# logi-edu.net
KiCad netlist of a schematic drawn in Altium Designer
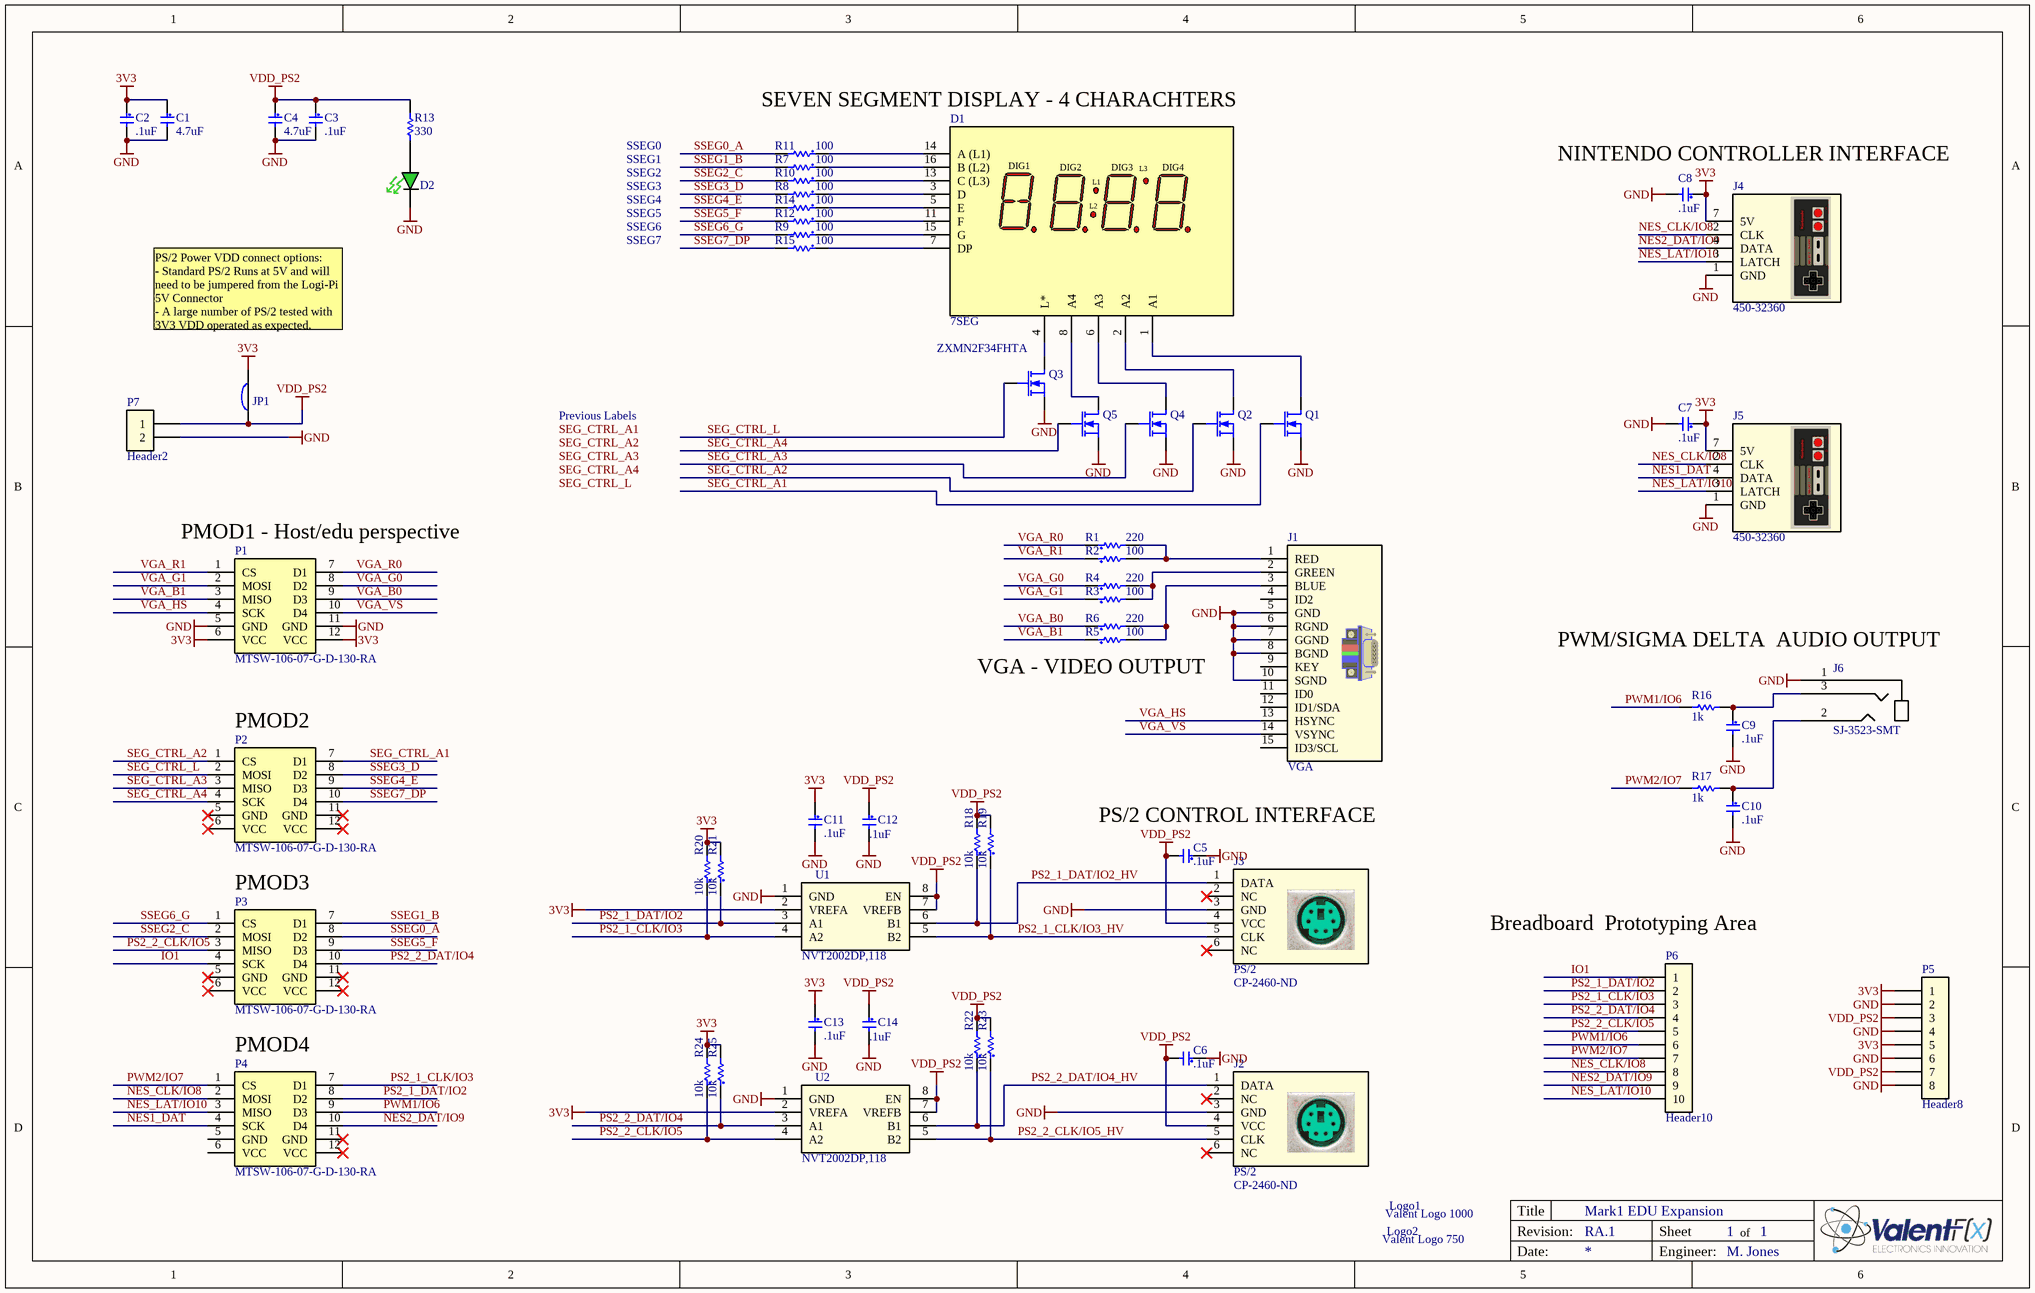
[diagram p0: logi-edu.SchDoc]

(export (version "E")
  (design (tool "Eeschema 10.0.6"))
  (components
    (comp (ref "C1")
      (value "4.7uF")
      (footprint "mRCL:C0603")
      (description "4.7uF 10volts Y5V +80-20% (MLCC) - SMD/SMT 0603")
      (fields
        (field (name "MANUFACTURER") "Murata")
        (field (name "MANUFACTURER PART NUMBER") "GRM188F51A475ZE20D")
      )
      (libsource (lib "mCapacitors") (part "C0603 - GRM188F51A475ZE20D"))
    )
    (comp (ref "C2")
      (value ".1uF")
      (footprint "mRCL:C0603")
      (description "0.1uF 50volts X7R 10% MLCC SMD/SMT 0603")
      (fields
        (field (name "MANUFACTURER") "Murata")
        (field (name "MANUFACTURER PART NUMBER") "GRM188R71H104KA93D")
      )
      (libsource (lib "mCapacitors") (part "C0603 - GRM188R71H104KA93D"))
    )
    (comp (ref "C3")
      (value ".1uF")
      (footprint "mRCL:C0603")
      (description "0.1uF 50volts X7R 10% MLCC SMD/SMT 0603")
      (fields
        (field (name "MANUFACTURER") "Murata")
        (field (name "MANUFACTURER PART NUMBER") "GRM188R71H104KA93D")
      )
      (libsource (lib "mCapacitors") (part "C0603 - GRM188R71H104KA93D"))
    )
    (comp (ref "C4")
      (value "4.7uF")
      (footprint "mRCL:C0603")
      (description "4.7uF 10volts Y5V +80-20% (MLCC) - SMD/SMT 0603")
      (fields
        (field (name "MANUFACTURER") "Murata")
        (field (name "MANUFACTURER PART NUMBER") "GRM188F51A475ZE20D")
      )
      (libsource (lib "mCapacitors") (part "C0603 - GRM188F51A475ZE20D"))
    )
    (comp (ref "C5")
      (value ".1uF")
      (footprint "mRCL:C0603")
      (description "0.1uF 50volts X7R 10% MLCC SMD/SMT 0603")
      (fields
        (field (name "MANUFACTURER") "Murata")
        (field (name "MANUFACTURER PART NUMBER") "GRM188R71H104KA93D")
      )
      (libsource (lib "mCapacitors") (part "C0603 - GRM188R71H104KA93D"))
    )
    (comp (ref "C6")
      (value ".1uF")
      (footprint "mRCL:C0603")
      (description "0.1uF 50volts X7R 10% MLCC SMD/SMT 0603")
      (fields
        (field (name "MANUFACTURER") "Murata")
        (field (name "MANUFACTURER PART NUMBER") "GRM188R71H104KA93D")
      )
      (libsource (lib "mCapacitors") (part "C0603 - GRM188R71H104KA93D"))
    )
    (comp (ref "C7")
      (value ".1uF")
      (footprint "mRCL:C0603")
      (description "0.1uF 50volts X7R 10% MLCC SMD/SMT 0603")
      (fields
        (field (name "MANUFACTURER") "Murata")
        (field (name "MANUFACTURER PART NUMBER") "GRM188R71H104KA93D")
      )
      (libsource (lib "mCapacitors") (part "C0603 - GRM188R71H104KA93D"))
    )
    (comp (ref "C8")
      (value ".1uF")
      (footprint "mRCL:C0603")
      (description "0.1uF 50volts X7R 10% MLCC SMD/SMT 0603")
      (fields
        (field (name "MANUFACTURER") "Murata")
        (field (name "MANUFACTURER PART NUMBER") "GRM188R71H104KA93D")
      )
      (libsource (lib "mCapacitors") (part "C0603 - GRM188R71H104KA93D"))
    )
    (comp (ref "C9")
      (value ".1uF")
      (footprint "mRCL:C0603")
      (description "0.1uF 50volts X7R 10% MLCC SMD/SMT 0603")
      (fields
        (field (name "MANUFACTURER") "Murata")
        (field (name "MANUFACTURER PART NUMBER") "GRM188R71H104KA93D")
      )
      (libsource (lib "mCapacitors") (part "C0603 - GRM188R71H104KA93D"))
    )
    (comp (ref "C10")
      (value ".1uF")
      (footprint "mRCL:C0603")
      (description "0.1uF 50volts X7R 10% MLCC SMD/SMT 0603")
      (fields
        (field (name "MANUFACTURER") "Murata")
        (field (name "MANUFACTURER PART NUMBER") "GRM188R71H104KA93D")
      )
      (libsource (lib "mCapacitors") (part "C0603 - GRM188R71H104KA93D"))
    )
    (comp (ref "C11")
      (value ".1uF")
      (footprint "mRCL:C0603")
      (description "0.1uF 50volts X7R 10% MLCC SMD/SMT 0603")
      (fields
        (field (name "MANUFACTURER") "Murata")
        (field (name "MANUFACTURER PART NUMBER") "GRM188R71H104KA93D")
      )
      (libsource (lib "mCapacitors") (part "C0603 - GRM188R71H104KA93D"))
    )
    (comp (ref "C12")
      (value ".1uF")
      (footprint "mRCL:C0603")
      (description "0.1uF 50volts X7R 10% MLCC SMD/SMT 0603")
      (fields
        (field (name "MANUFACTURER") "Murata")
        (field (name "MANUFACTURER PART NUMBER") "GRM188R71H104KA93D")
      )
      (libsource (lib "mCapacitors") (part "C0603 - GRM188R71H104KA93D"))
    )
    (comp (ref "C13")
      (value ".1uF")
      (footprint "mRCL:C0603")
      (description "0.1uF 50volts X7R 10% MLCC SMD/SMT 0603")
      (fields
        (field (name "MANUFACTURER") "Murata")
        (field (name "MANUFACTURER PART NUMBER") "GRM188R71H104KA93D")
      )
      (libsource (lib "mCapacitors") (part "C0603 - GRM188R71H104KA93D"))
    )
    (comp (ref "C14")
      (value ".1uF")
      (footprint "mRCL:C0603")
      (description "0.1uF 50volts X7R 10% MLCC SMD/SMT 0603")
      (fields
        (field (name "MANUFACTURER") "Murata")
        (field (name "MANUFACTURER PART NUMBER") "GRM188R71H104KA93D")
      )
      (libsource (lib "mCapacitors") (part "C0603 - GRM188R71H104KA93D"))
    )
    (comp (ref "D1")
      (value "7SEG")
      (footprint "LED - SSEG - LTC-4727JR")
      (description "LED Displays & Accessories 4 Digit, Red Low Current")
      (fields (field (name "MANUFACTURER") "Lite-On") (field (name "MANUFACTURER PART NUMBER") "LTC-4727JR"))
      (libsource (lib "eDiode") (part "LED - SSEG - LTC-4727JR"))
    )
    (comp (ref "D2")
      (value "LED 1.6X0.8MM 570NM GRN CLR SMD")
      (footprint "LED_0603 - GREEN")
      (fields
        (field (name "MANUFACTURER") "Kingbright Corp")
        (field (name "MANUFACTURER PART NUMBER") "APT1608CGCK")
      )
      (libsource (lib "eDiode") (part "APT1608CGCK"))
    )
    (comp (ref "J1")
      (value "VGA")
      (footprint "econnector:1-1734530-1")
      (description "CONN HD D-SUB RCPT R/A 15POS")
      (fields
        (field (name "MANUFACTURER") "TE Connectivity")
        (field (name "MANUFACTURER PART NUMBER") "1-1734530-1")
      )
      (libsource (lib "eConnector") (part "VGA - 1-1734530-1"))
    )
    (comp (ref "J2")
      (value "PS/2")
      (footprint "mconnector:MD-60S - PS/2")
      (description "CONN MINIDIN RECPT UNSHIELD 6POS - PS/2 mouse - keybaord")
      (fields
        (field (name "MANUFACTURER") "CUI Inc")
        (field (name "MANUFACTURER PART NUMBER") "MD-60S")
        (field (name "SUPPLIER PART NUMBER 1") "CP-2460-ND")
      )
      (libsource (lib "mConnector") (part "Con - D-60S"))
    )
    (comp (ref "J3")
      (value "PS/2")
      (footprint "mconnector:MD-60S - PS/2")
      (description "CONN MINIDIN RECPT UNSHIELD 6POS - PS/2 mouse - keybaord")
      (fields
        (field (name "MANUFACTURER") "CUI Inc")
        (field (name "MANUFACTURER PART NUMBER") "MD-60S")
        (field (name "SUPPLIER PART NUMBER 1") "CP-2460-ND")
      )
      (libsource (lib "mConnector") (part "Con - D-60S"))
    )
    (comp (ref "J4")
      (value "450-32360")
      (footprint "NES - 450-32360")
      (description "NES CONTROLLER SOCKET")
      (fields (field (name "MANUFACTURER") "Parallax Inc"))
      (libsource (lib "mConnector") (part "450-32360"))
    )
    (comp (ref "J5")
      (value "450-32360")
      (footprint "NES - 450-32360")
      (description "NES CONTROLLER SOCKET")
      (fields (field (name "MANUFACTURER") "Parallax Inc"))
      (libsource (lib "mConnector") (part "450-32360"))
    )
    (comp (ref "J6")
      (value "SJ-3523-SMT")
      (footprint "SJ-3523-SMT")
      (description "CONN AUDIO JACK 3.5MM STEREO SMD")
      (fields (field (name "MANUFACTURER") "CUI Inc") (field (name "SOURCE") "Digikey"))
      (libsource (lib "eConnector") (part "SJ-3523-SMT"))
    )
    (comp (ref "JP1")
      (value "Solder Jumper-NC")
      (footprint "SOLDER_JUMPER-NC")
      (description "Solder/Configuration Jumper")
      (fields (field (name "MANUFACTURER") "n/a"))
      (libsource (lib "mConnector") (part "Solder Jumper-NC"))
    )
    (comp (ref "Logo1")
      (value "Valent Logo 1000")
      (footprint "ValentFX_1000")
      (libsource (lib "mLogos") (part "Valent Logo 1000"))
    )
    (comp (ref "Logo2")
      (value "Valent Logo 750")
      (footprint "ValentFX_750")
      (libsource (lib "mLogos") (part "Valent Logo 750"))
    )
    (comp (ref "P1")
      (value "MTSW-106-07-G-D-130-RA")
      (footprint "mconnector:PMOD HEADER - Male")
      (description "Samtec Male Conn Unshrouded Header HDR 12 POS 2.54mm Solder RA Thru-Hole")
      (fields (field (name "MANUFACTURER") "Samtec"))
      (libsource (lib "mConnector") (part "P-MOD - MTSW-106-07-G-D-130-RA"))
    )
    (comp (ref "P2")
      (value "MTSW-106-07-G-D-130-RA")
      (footprint "mconnector:PMOD HEADER - Male")
      (description "Samtec Male Conn Unshrouded Header HDR 12 POS 2.54mm Solder RA Thru-Hole")
      (fields (field (name "MANUFACTURER") "Samtec"))
      (libsource (lib "mConnector") (part "P-MOD - MTSW-106-07-G-D-130-RA"))
    )
    (comp (ref "P3")
      (value "MTSW-106-07-G-D-130-RA")
      (footprint "mconnector:PMOD HEADER - Male")
      (description "Samtec Male Conn Unshrouded Header HDR 12 POS 2.54mm Solder RA Thru-Hole")
      (fields (field (name "MANUFACTURER") "Samtec"))
      (libsource (lib "mConnector") (part "P-MOD - MTSW-106-07-G-D-130-RA"))
    )
    (comp (ref "P4")
      (value "MTSW-106-07-G-D-130-RA")
      (footprint "mconnector:PMOD HEADER - Male")
      (description "Samtec Male Conn Unshrouded Header HDR 12 POS 2.54mm Solder RA Thru-Hole")
      (fields (field (name "MANUFACTURER") "Samtec"))
      (libsource (lib "mConnector") (part "P-MOD - MTSW-106-07-G-D-130-RA"))
    )
    (comp (ref "P5")
      (value "Header8")
      (footprint "HEADER_8_40_100THRU SIP")
      (description "Header 8 pin")
      (libsource (lib "mConnector") (part "Header8"))
    )
    (comp (ref "P6")
      (value "Header10")
      (footprint "HEADER_10_40_100THRU SIP")
      (description "Header 10 pin")
      (libsource (lib "mConnector") (part "Header10"))
    )
    (comp (ref "P7")
      (value "Header2")
      (footprint "HEADER_2_40_100 THRU SIP")
      (description "Header 2 pin")
      (libsource (lib "mConnector") (part "Header2"))
    )
    (comp (ref "Q1")
      (value "ZXMN2F34FHTA")
      (footprint "SOT-23")
      (description "MOSFET N-CHAN 20V SOT23-3")
      (fields (field (name "MANUFACTURER") "Diodes/Zetex"))
      (libsource (lib "eTransistor") (part "ZXMN2F34FHTA"))
    )
    (comp (ref "Q2")
      (value "ZXMN2F34FHTA")
      (footprint "SOT-23")
      (description "MOSFET N-CHAN 20V SOT23-3")
      (fields (field (name "MANUFACTURER") "Diodes/Zetex"))
      (libsource (lib "eTransistor") (part "ZXMN2F34FHTA"))
    )
    (comp (ref "Q3")
      (value "ZXMN2F34FHTA")
      (footprint "SOT-23")
      (description "MOSFET N-CHAN 20V SOT23-3")
      (fields (field (name "MANUFACTURER") "Diodes/Zetex"))
      (libsource (lib "eTransistor") (part "ZXMN2F34FHTA"))
    )
    (comp (ref "Q4")
      (value "ZXMN2F34FHTA")
      (footprint "SOT-23")
      (description "MOSFET N-CHAN 20V SOT23-3")
      (fields (field (name "MANUFACTURER") "Diodes/Zetex"))
      (libsource (lib "eTransistor") (part "ZXMN2F34FHTA"))
    )
    (comp (ref "Q5")
      (value "ZXMN2F34FHTA")
      (footprint "SOT-23")
      (description "MOSFET N-CHAN 20V SOT23-3")
      (fields (field (name "MANUFACTURER") "Diodes/Zetex"))
      (libsource (lib "eTransistor") (part "ZXMN2F34FHTA"))
    )
    (comp (ref "R1")
      (value "220")
      (footprint "mRCL:R0603")
      (description "220 - thick Film Resistors - SMD 0603 220ohms 1% Tol")
      (fields
        (field (name "MANUFACTURER") "Panasonic - ECG")
        (field (name "MANUFACTURER PART NUMBER") "ERJ-3EKF2200V")
      )
      (libsource (lib "mResistors") (part "R0603 - ERJ-3EKF2200V"))
    )
    (comp (ref "R2")
      (value "100")
      (footprint "mRCL:R0603")
      (description "100 ohms 1% Thick Film Resistors - SMD 1/10watt")
      (fields
        (field (name "MANUFACTURER") "Vishay/Dale")
        (field (name "MANUFACTURER PART NUMBER") "CRCW0603100RFKEA")
      )
      (libsource (lib "mResistors") (part "R0603 - CRCW0603100RFKEA"))
    )
    (comp (ref "R3")
      (value "100")
      (footprint "mRCL:R0603")
      (description "100 ohms 1% Thick Film Resistors - SMD 1/10watt")
      (fields
        (field (name "MANUFACTURER") "Vishay/Dale")
        (field (name "MANUFACTURER PART NUMBER") "CRCW0603100RFKEA")
      )
      (libsource (lib "mResistors") (part "R0603 - CRCW0603100RFKEA"))
    )
    (comp (ref "R4")
      (value "220")
      (footprint "mRCL:R0603")
      (description "220 - thick Film Resistors - SMD 0603 220ohms 1% Tol")
      (fields
        (field (name "MANUFACTURER") "Panasonic - ECG")
        (field (name "MANUFACTURER PART NUMBER") "ERJ-3EKF2200V")
      )
      (libsource (lib "mResistors") (part "R0603 - ERJ-3EKF2200V"))
    )
    (comp (ref "R5")
      (value "100")
      (footprint "mRCL:R0603")
      (description "100 ohms 1% Thick Film Resistors - SMD 1/10watt")
      (fields
        (field (name "MANUFACTURER") "Vishay/Dale")
        (field (name "MANUFACTURER PART NUMBER") "CRCW0603100RFKEA")
      )
      (libsource (lib "mResistors") (part "R0603 - CRCW0603100RFKEA"))
    )
    (comp (ref "R6")
      (value "220")
      (footprint "mRCL:R0603")
      (description "220 - thick Film Resistors - SMD 0603 220ohms 1% Tol")
      (fields
        (field (name "MANUFACTURER") "Panasonic - ECG")
        (field (name "MANUFACTURER PART NUMBER") "ERJ-3EKF2200V")
      )
      (libsource (lib "mResistors") (part "R0603 - ERJ-3EKF2200V"))
    )
    (comp (ref "R7")
      (value "100")
      (footprint "R0603")
      (description "RES 10.0K OHM 1/10W 1% 0603 SMD")
      (fields
        (field (name "MANUFACTURER") "Panasonic - ECG")
        (field (name "MANUFACTURER PART NUMBER") "ERJ-3EKF1002V")
      )
      (libsource (lib "myGeneral") (part "Res-Eli"))
    )
    (comp (ref "R8")
      (value "100")
      (footprint "R0603")
      (description "RES 10.0K OHM 1/10W 1% 0603 SMD")
      (fields
        (field (name "MANUFACTURER") "Panasonic - ECG")
        (field (name "MANUFACTURER PART NUMBER") "ERJ-3EKF1002V")
      )
      (libsource (lib "myGeneral") (part "Res-Eli"))
    )
    (comp (ref "R9")
      (value "100")
      (footprint "R0603")
      (description "RES 10.0K OHM 1/10W 1% 0603 SMD")
      (fields
        (field (name "MANUFACTURER") "Panasonic - ECG")
        (field (name "MANUFACTURER PART NUMBER") "ERJ-3EKF1002V")
      )
      (libsource (lib "myGeneral") (part "Res-Eli"))
    )
    (comp (ref "R10")
      (value "100")
      (footprint "R0603")
      (description "RES 10.0K OHM 1/10W 1% 0603 SMD")
      (fields
        (field (name "MANUFACTURER") "Panasonic - ECG")
        (field (name "MANUFACTURER PART NUMBER") "ERJ-3EKF1002V")
      )
      (libsource (lib "myGeneral") (part "Res-Eli"))
    )
    (comp (ref "R11")
      (value "100")
      (footprint "R0603")
      (description "RES 10.0K OHM 1/10W 1% 0603 SMD")
      (fields
        (field (name "MANUFACTURER") "Panasonic - ECG")
        (field (name "MANUFACTURER PART NUMBER") "ERJ-3EKF1002V")
      )
      (libsource (lib "myGeneral") (part "Res-Eli"))
    )
    (comp (ref "R12")
      (value "100")
      (footprint "R0603")
      (description "RES 10.0K OHM 1/10W 1% 0603 SMD")
      (fields
        (field (name "MANUFACTURER") "Panasonic - ECG")
        (field (name "MANUFACTURER PART NUMBER") "ERJ-3EKF1002V")
      )
      (libsource (lib "myGeneral") (part "Res-Eli"))
    )
    (comp (ref "R13")
      (value "330")
      (footprint "R0603")
      (description "RES 330 OHM 1/10W 1% 0603 SMD")
      (fields
        (field (name "MANUFACTURER") "Panasonic - ECG")
        (field (name "MANUFACTURER PART NUMBER") "ERJ-3EKF3300V")
      )
      (libsource (lib "eResistors") (part "ERJ-3EKF3300V"))
    )
    (comp (ref "R14")
      (value "100")
      (footprint "R0603")
      (description "RES 10.0K OHM 1/10W 1% 0603 SMD")
      (fields
        (field (name "MANUFACTURER") "Panasonic - ECG")
        (field (name "MANUFACTURER PART NUMBER") "ERJ-3EKF1002V")
      )
      (libsource (lib "myGeneral") (part "Res-Eli"))
    )
    (comp (ref "R15")
      (value "100")
      (footprint "R0603")
      (description "RES 10.0K OHM 1/10W 1% 0603 SMD")
      (fields
        (field (name "MANUFACTURER") "Panasonic - ECG")
        (field (name "MANUFACTURER PART NUMBER") "ERJ-3EKF1002V")
      )
      (libsource (lib "myGeneral") (part "Res-Eli"))
    )
    (comp (ref "R16")
      (value "1k")
      (footprint "R0603")
      (description "RES 1.00K OHM 1/10W 1% 0603 SMD")
      (fields
        (field (name "MANUFACTURER") "Panasonic - ECG")
        (field (name "MANUFACTURER PART NUMBER") "ERJ-3EKF1001V")
      )
      (libsource (lib "eResistors") (part "ERJ-3EKF1001V"))
    )
    (comp (ref "R17")
      (value "1k")
      (footprint "R0603")
      (description "RES 1.00K OHM 1/10W 1% 0603 SMD")
      (fields
        (field (name "MANUFACTURER") "Panasonic - ECG")
        (field (name "MANUFACTURER PART NUMBER") "ERJ-3EKF1001V")
      )
      (libsource (lib "eResistors") (part "ERJ-3EKF1001V"))
    )
    (comp (ref "R18")
      (value "10k")
      (footprint "mRCL:R0603")
      (description "10k Thick Film Resistors - SMD 1/10watt 10Kohms 1%")
      (fields
        (field (name "MANUFACTURER") "Vishay Dale")
        (field (name "MANUFACTURER PART NUMBER") "CRCW060310K0FKEA")
      )
      (libsource (lib "mResistors") (part "R0603 - CRCW060310K0FKEA"))
    )
    (comp (ref "R19")
      (value "10k")
      (footprint "mRCL:R0603")
      (description "10k Thick Film Resistors - SMD 1/10watt 10Kohms 1%")
      (fields
        (field (name "MANUFACTURER") "Vishay Dale")
        (field (name "MANUFACTURER PART NUMBER") "CRCW060310K0FKEA")
      )
      (libsource (lib "mResistors") (part "R0603 - CRCW060310K0FKEA"))
    )
    (comp (ref "R20")
      (value "10k")
      (footprint "mRCL:R0603")
      (description "10k Thick Film Resistors - SMD 1/10watt 10Kohms 1%")
      (fields
        (field (name "MANUFACTURER") "Vishay Dale")
        (field (name "MANUFACTURER PART NUMBER") "CRCW060310K0FKEA")
      )
      (libsource (lib "mResistors") (part "R0603 - CRCW060310K0FKEA"))
    )
    (comp (ref "R21")
      (value "10k")
      (footprint "mRCL:R0603")
      (description "10k Thick Film Resistors - SMD 1/10watt 10Kohms 1%")
      (fields
        (field (name "MANUFACTURER") "Vishay Dale")
        (field (name "MANUFACTURER PART NUMBER") "CRCW060310K0FKEA")
      )
      (libsource (lib "mResistors") (part "R0603 - CRCW060310K0FKEA"))
    )
    (comp (ref "R22")
      (value "10k")
      (footprint "mRCL:R0603")
      (description "10k Thick Film Resistors - SMD 1/10watt 10Kohms 1%")
      (fields
        (field (name "MANUFACTURER") "Vishay Dale")
        (field (name "MANUFACTURER PART NUMBER") "CRCW060310K0FKEA")
      )
      (libsource (lib "mResistors") (part "R0603 - CRCW060310K0FKEA"))
    )
    (comp (ref "R23")
      (value "10k")
      (footprint "mRCL:R0603")
      (description "10k Thick Film Resistors - SMD 1/10watt 10Kohms 1%")
      (fields
        (field (name "MANUFACTURER") "Vishay Dale")
        (field (name "MANUFACTURER PART NUMBER") "CRCW060310K0FKEA")
      )
      (libsource (lib "mResistors") (part "R0603 - CRCW060310K0FKEA"))
    )
    (comp (ref "R24")
      (value "10k")
      (footprint "mRCL:R0603")
      (description "10k Thick Film Resistors - SMD 1/10watt 10Kohms 1%")
      (fields
        (field (name "MANUFACTURER") "Vishay Dale")
        (field (name "MANUFACTURER PART NUMBER") "CRCW060310K0FKEA")
      )
      (libsource (lib "mResistors") (part "R0603 - CRCW060310K0FKEA"))
    )
    (comp (ref "R25")
      (value "10k")
      (footprint "mRCL:R0603")
      (description "10k Thick Film Resistors - SMD 1/10watt 10Kohms 1%")
      (fields
        (field (name "MANUFACTURER") "Vishay Dale")
        (field (name "MANUFACTURER PART NUMBER") "CRCW060310K0FKEA")
      )
      (libsource (lib "mResistors") (part "R0603 - CRCW060310K0FKEA"))
    )
    (comp (ref "U1")
      (value "NVT2002DP,118")
      (footprint "NVT2002DP,118 - TSOP65P490X110-8L")
      (description "Translation - Open Drain - 2 Lines - Voltage Levels Interface IC")
      (fields (field (name "MANUFACTURER") "NXP Semiconductors"))
      (libsource (lib "mIC") (part "NVT2002DP,118"))
    )
    (comp (ref "U2")
      (value "NVT2002DP,118")
      (footprint "NVT2002DP,118 - TSOP65P490X110-8L")
      (description "Translation - Open Drain - 2 Lines - Voltage Levels Interface IC")
      (fields (field (name "MANUFACTURER") "NXP Semiconductors"))
      (libsource (lib "mIC") (part "NVT2002DP,118"))
    )
  )
  (nets
    (net (code "1") (name "/IO1") (class "Default")
      (node (ref "P3") (pin "4") (pinfunction "SCK_4") (pintype "power_in"))
      (node (ref "P6") (pin "1") (pinfunction "1_1") (pintype "passive"))
    )
    (net (code "2") (name "/NES1_DAT") (class "Default")
      (node (ref "J5") (pin "4") (pinfunction "DATA_4") (pintype "passive"))
      (node (ref "P4") (pin "4") (pinfunction "SCK_4") (pintype "power_in"))
    )
    (net (code "3") (name "/NES2_DAT{slash}IO9") (class "Default")
      (node (ref "J4") (pin "4") (pinfunction "DATA_4") (pintype "passive"))
      (node (ref "P4") (pin "10") (pinfunction "D4_10") (pintype "power_in"))
      (node (ref "P6") (pin "9") (pinfunction "9_9") (pintype "passive"))
    )
    (net (code "4") (name "/NES_CLK{slash}IO8") (class "Default")
      (node (ref "J4") (pin "2") (pinfunction "CLK_2") (pintype "passive"))
      (node (ref "J5") (pin "2") (pinfunction "CLK_2") (pintype "passive"))
      (node (ref "P4") (pin "2") (pinfunction "MOSI_2") (pintype "power_in"))
      (node (ref "P6") (pin "8") (pinfunction "8_8") (pintype "passive"))
    )
    (net (code "5") (name "/NES_LAT{slash}IO10") (class "Default")
      (node (ref "J4") (pin "3") (pinfunction "LATCH_3") (pintype "passive"))
      (node (ref "J5") (pin "3") (pinfunction "LATCH_3") (pintype "passive"))
      (node (ref "P4") (pin "3") (pinfunction "MISO_3") (pintype "power_in"))
      (node (ref "P6") (pin "10") (pinfunction "10_10") (pintype "passive"))
    )
    (net (code "6") (name "/PS2_1_CLK{slash}IO3") (class "Default")
      (node (ref "P4") (pin "7") (pinfunction "D1_7") (pintype "power_in"))
      (node (ref "P6") (pin "3") (pinfunction "3_3") (pintype "passive"))
      (node (ref "R20") (pin "1") (pinfunction "1_1") (pintype "passive"))
      (node (ref "U1") (pin "4") (pinfunction "A2_4") (pintype "passive"))
    )
    (net (code "7") (name "/PS2_1_CLK{slash}IO3_HV") (class "Default")
      (node (ref "J3") (pin "5") (pinfunction "CLK_5") (pintype "passive"))
      (node (ref "R19") (pin "1") (pinfunction "1_1") (pintype "passive"))
      (node (ref "U1") (pin "5") (pinfunction "B2_5") (pintype "passive"))
    )
    (net (code "8") (name "/PS2_1_DAT{slash}IO2") (class "Default")
      (node (ref "P4") (pin "8") (pinfunction "D2_8") (pintype "power_in"))
      (node (ref "P6") (pin "2") (pinfunction "2_2") (pintype "passive"))
      (node (ref "R21") (pin "1") (pinfunction "1_1") (pintype "passive"))
      (node (ref "U1") (pin "3") (pinfunction "A1_3") (pintype "passive"))
    )
    (net (code "9") (name "/PS2_1_DAT{slash}IO2_HV") (class "Default")
      (node (ref "J3") (pin "1") (pinfunction "DATA_1") (pintype "passive"))
      (node (ref "R18") (pin "1") (pinfunction "1_1") (pintype "passive"))
      (node (ref "U1") (pin "6") (pinfunction "B1_6") (pintype "passive"))
    )
    (net (code "10") (name "/PS2_2_CLK{slash}IO5") (class "Default")
      (node (ref "P3") (pin "3") (pinfunction "MISO_3") (pintype "power_in"))
      (node (ref "P6") (pin "5") (pinfunction "5_5") (pintype "passive"))
      (node (ref "R24") (pin "1") (pinfunction "1_1") (pintype "passive"))
      (node (ref "U2") (pin "4") (pinfunction "A2_4") (pintype "passive"))
    )
    (net (code "11") (name "/PS2_2_CLK{slash}IO5_HV") (class "Default")
      (node (ref "J2") (pin "5") (pinfunction "CLK_5") (pintype "passive"))
      (node (ref "R23") (pin "1") (pinfunction "1_1") (pintype "passive"))
      (node (ref "U2") (pin "5") (pinfunction "B2_5") (pintype "passive"))
    )
    (net (code "12") (name "/PS2_2_DAT{slash}IO4") (class "Default")
      (node (ref "P3") (pin "10") (pinfunction "D4_10") (pintype "power_in"))
      (node (ref "P6") (pin "4") (pinfunction "4_4") (pintype "passive"))
      (node (ref "R25") (pin "1") (pinfunction "1_1") (pintype "passive"))
      (node (ref "U2") (pin "3") (pinfunction "A1_3") (pintype "passive"))
    )
    (net (code "13") (name "/PS2_2_DAT{slash}IO4_HV") (class "Default")
      (node (ref "J2") (pin "1") (pinfunction "DATA_1") (pintype "passive"))
      (node (ref "R22") (pin "1") (pinfunction "1_1") (pintype "passive"))
      (node (ref "U2") (pin "6") (pinfunction "B1_6") (pintype "passive"))
    )
    (net (code "14") (name "/PWM1{slash}IO6") (class "Default")
      (node (ref "P4") (pin "9") (pinfunction "D3_9") (pintype "power_in"))
      (node (ref "P6") (pin "6") (pinfunction "6_6") (pintype "passive"))
      (node (ref "R16") (pin "1") (pinfunction "1_1") (pintype "passive"))
    )
    (net (code "15") (name "/PWM2{slash}IO7") (class "Default")
      (node (ref "P4") (pin "1") (pinfunction "CS_1") (pintype "power_in"))
      (node (ref "P6") (pin "7") (pinfunction "7_7") (pintype "passive"))
      (node (ref "R17") (pin "1") (pinfunction "1_1") (pintype "passive"))
    )
    (net (code "16") (name "/SEG_CTRL_A1") (class "Default")
      (node (ref "P2") (pin "7") (pinfunction "D1_7") (pintype "power_in"))
      (node (ref "Q1") (pin "1") (pinfunction "G_1") (pintype "passive"))
    )
    (net (code "17") (name "/SEG_CTRL_A2") (class "Default")
      (node (ref "P2") (pin "1") (pinfunction "CS_1") (pintype "power_in"))
      (node (ref "Q2") (pin "1") (pinfunction "G_1") (pintype "passive"))
    )
    (net (code "18") (name "/SEG_CTRL_A3") (class "Default")
      (node (ref "P2") (pin "3") (pinfunction "MISO_3") (pintype "power_in"))
      (node (ref "Q4") (pin "1") (pinfunction "G_1") (pintype "passive"))
    )
    (net (code "19") (name "/SEG_CTRL_A4") (class "Default")
      (node (ref "P2") (pin "4") (pinfunction "SCK_4") (pintype "power_in"))
      (node (ref "Q5") (pin "1") (pinfunction "G_1") (pintype "passive"))
    )
    (net (code "20") (name "/SEG_CTRL_L") (class "Default")
      (node (ref "P2") (pin "2") (pinfunction "MOSI_2") (pintype "power_in"))
      (node (ref "Q3") (pin "1") (pinfunction "G_1") (pintype "passive"))
    )
    (net (code "21") (name "/SSEG0_A") (class "Default")
      (node (ref "P3") (pin "8") (pinfunction "D2_8") (pintype "power_in"))
      (node (ref "R11") (pin "2") (pinfunction "2_2") (pintype "passive"))
    )
    (net (code "22") (name "/SSEG1_B") (class "Default")
      (node (ref "P3") (pin "7") (pinfunction "D1_7") (pintype "power_in"))
      (node (ref "R7") (pin "2") (pinfunction "2_2") (pintype "passive"))
    )
    (net (code "23") (name "/SSEG2_C") (class "Default")
      (node (ref "P3") (pin "2") (pinfunction "MOSI_2") (pintype "power_in"))
      (node (ref "R10") (pin "2") (pinfunction "2_2") (pintype "passive"))
    )
    (net (code "24") (name "/SSEG3_D") (class "Default")
      (node (ref "P2") (pin "8") (pinfunction "D2_8") (pintype "power_in"))
      (node (ref "R8") (pin "2") (pinfunction "2_2") (pintype "passive"))
    )
    (net (code "25") (name "/SSEG4_E") (class "Default")
      (node (ref "P2") (pin "9") (pinfunction "D3_9") (pintype "power_in"))
      (node (ref "R14") (pin "2") (pinfunction "2_2") (pintype "passive"))
    )
    (net (code "26") (name "/SSEG5_F") (class "Default")
      (node (ref "P3") (pin "9") (pinfunction "D3_9") (pintype "power_in"))
      (node (ref "R12") (pin "2") (pinfunction "2_2") (pintype "passive"))
    )
    (net (code "27") (name "/SSEG6_G") (class "Default")
      (node (ref "P3") (pin "1") (pinfunction "CS_1") (pintype "power_in"))
      (node (ref "R9") (pin "2") (pinfunction "2_2") (pintype "passive"))
    )
    (net (code "28") (name "/SSEG7_DP") (class "Default")
      (node (ref "P2") (pin "10") (pinfunction "D4_10") (pintype "power_in"))
      (node (ref "R15") (pin "2") (pinfunction "2_2") (pintype "passive"))
    )
    (net (code "29") (name "/VGA_B0") (class "Default")
      (node (ref "P1") (pin "9") (pinfunction "D3_9") (pintype "power_in"))
      (node (ref "R6") (pin "1") (pinfunction "1_1") (pintype "passive"))
    )
    (net (code "30") (name "/VGA_B1") (class "Default")
      (node (ref "P1") (pin "3") (pinfunction "MISO_3") (pintype "power_in"))
      (node (ref "R5") (pin "1") (pinfunction "1_1") (pintype "passive"))
    )
    (net (code "31") (name "/VGA_G0") (class "Default")
      (node (ref "P1") (pin "8") (pinfunction "D2_8") (pintype "power_in"))
      (node (ref "R4") (pin "1") (pinfunction "1_1") (pintype "passive"))
    )
    (net (code "32") (name "/VGA_G1") (class "Default")
      (node (ref "P1") (pin "2") (pinfunction "MOSI_2") (pintype "power_in"))
      (node (ref "R3") (pin "1") (pinfunction "1_1") (pintype "passive"))
    )
    (net (code "33") (name "/VGA_HS") (class "Default")
      (node (ref "J1") (pin "13") (pinfunction "HSYNC_13") (pintype "passive"))
      (node (ref "P1") (pin "4") (pinfunction "SCK_4") (pintype "power_in"))
    )
    (net (code "34") (name "/VGA_R0") (class "Default")
      (node (ref "P1") (pin "7") (pinfunction "D1_7") (pintype "power_in"))
      (node (ref "R1") (pin "1") (pinfunction "1_1") (pintype "passive"))
    )
    (net (code "35") (name "/VGA_R1") (class "Default")
      (node (ref "P1") (pin "1") (pinfunction "CS_1") (pintype "power_in"))
      (node (ref "R2") (pin "1") (pinfunction "1_1") (pintype "passive"))
    )
    (net (code "36") (name "/VGA_VS") (class "Default")
      (node (ref "J1") (pin "14") (pinfunction "VSYNC_14") (pintype "passive"))
      (node (ref "P1") (pin "10") (pinfunction "D4_10") (pintype "power_in"))
    )
    (net (code "37") (name "3V3") (class "Default")
      (node (ref "C1") (pin "1") (pinfunction "1_1") (pintype "passive"))
      (node (ref "C11") (pin "1") (pinfunction "1_1") (pintype "passive"))
      (node (ref "C13") (pin "1") (pinfunction "1_1") (pintype "passive"))
      (node (ref "C2") (pin "1") (pinfunction "1_1") (pintype "passive"))
      (node (ref "C7") (pin "1") (pinfunction "1_1") (pintype "passive"))
      (node (ref "C8") (pin "1") (pinfunction "1_1") (pintype "passive"))
      (node (ref "J4") (pin "7") (pinfunction "5V_7") (pintype "passive"))
      (node (ref "J5") (pin "7") (pinfunction "5V_7") (pintype "passive"))
      (node (ref "JP1") (pin "2") (pinfunction "2_2") (pintype "passive"))
      (node (ref "P1") (pin "12") (pinfunction "VCC_12") (pintype "power_in"))
      (node (ref "P1") (pin "6") (pinfunction "VCC_6") (pintype "power_in"))
      (node (ref "P5") (pin "1") (pinfunction "1_1") (pintype "passive"))
      (node (ref "P5") (pin "5") (pinfunction "5_5") (pintype "passive"))
      (node (ref "R20") (pin "2") (pinfunction "2_2") (pintype "passive"))
      (node (ref "R21") (pin "2") (pinfunction "2_2") (pintype "passive"))
      (node (ref "R24") (pin "2") (pinfunction "2_2") (pintype "passive"))
      (node (ref "R25") (pin "2") (pinfunction "2_2") (pintype "passive"))
      (node (ref "U1") (pin "2") (pinfunction "VREFA_2") (pintype "passive"))
      (node (ref "U2") (pin "2") (pinfunction "VREFA_2") (pintype "passive"))
    )
    (net (code "38") (name "GND") (class "Default")
      (node (ref "C1") (pin "2") (pinfunction "2_2") (pintype "passive"))
      (node (ref "C10") (pin "2") (pinfunction "2_2") (pintype "passive"))
      (node (ref "C11") (pin "2") (pinfunction "2_2") (pintype "passive"))
      (node (ref "C12") (pin "2") (pinfunction "2_2") (pintype "passive"))
      (node (ref "C13") (pin "2") (pinfunction "2_2") (pintype "passive"))
      (node (ref "C14") (pin "2") (pinfunction "2_2") (pintype "passive"))
      (node (ref "C2") (pin "2") (pinfunction "2_2") (pintype "passive"))
      (node (ref "C3") (pin "2") (pinfunction "2_2") (pintype "passive"))
      (node (ref "C4") (pin "2") (pinfunction "2_2") (pintype "passive"))
      (node (ref "C5") (pin "1") (pinfunction "1_1") (pintype "passive"))
      (node (ref "C6") (pin "1") (pinfunction "1_1") (pintype "passive"))
      (node (ref "C7") (pin "2") (pinfunction "2_2") (pintype "passive"))
      (node (ref "C8") (pin "2") (pinfunction "2_2") (pintype "passive"))
      (node (ref "C9") (pin "2") (pinfunction "2_2") (pintype "passive"))
      (node (ref "D2") (pin "C") (pinfunction "C_C") (pintype "passive"))
      (node (ref "J1") (pin "10") (pinfunction "SGND_10") (pintype "passive"))
      (node (ref "J1") (pin "5") (pinfunction "GND_5") (pintype "passive"))
      (node (ref "J1") (pin "6") (pinfunction "RGND_6") (pintype "passive"))
      (node (ref "J1") (pin "7") (pinfunction "GGND_7") (pintype "passive"))
      (node (ref "J1") (pin "8") (pinfunction "BGND_8") (pintype "passive"))
      (node (ref "J2") (pin "3") (pinfunction "GND_3") (pintype "passive"))
      (node (ref "J3") (pin "3") (pinfunction "GND_3") (pintype "passive"))
      (node (ref "J4") (pin "1") (pinfunction "GND_1") (pintype "passive"))
      (node (ref "J5") (pin "1") (pinfunction "GND_1") (pintype "passive"))
      (node (ref "J6") (pin "1") (pinfunction "1_1") (pintype "passive"))
      (node (ref "P1") (pin "11") (pinfunction "GND_11") (pintype "power_in"))
      (node (ref "P1") (pin "5") (pinfunction "GND_5") (pintype "power_in"))
      (node (ref "P5") (pin "2") (pinfunction "2_2") (pintype "passive"))
      (node (ref "P5") (pin "4") (pinfunction "4_4") (pintype "passive"))
      (node (ref "P5") (pin "6") (pinfunction "6_6") (pintype "passive"))
      (node (ref "P5") (pin "8") (pinfunction "8_8") (pintype "passive"))
      (node (ref "P7") (pin "2") (pinfunction "2_2") (pintype "passive"))
      (node (ref "Q1") (pin "2") (pinfunction "2_2") (pintype "passive"))
      (node (ref "Q2") (pin "2") (pinfunction "2_2") (pintype "passive"))
      (node (ref "Q3") (pin "2") (pinfunction "2_2") (pintype "passive"))
      (node (ref "Q4") (pin "2") (pinfunction "2_2") (pintype "passive"))
      (node (ref "Q5") (pin "2") (pinfunction "2_2") (pintype "passive"))
      (node (ref "U1") (pin "1") (pinfunction "GND_1") (pintype "passive"))
      (node (ref "U2") (pin "1") (pinfunction "GND_1") (pintype "passive"))
    )
    (net (code "39") (name "Net-(C9-Pad1)") (class "Default")
      (node (ref "C9") (pin "1") (pinfunction "1_1") (pintype "passive"))
      (node (ref "J6") (pin "3") (pinfunction "3_3") (pintype "passive"))
      (node (ref "R16") (pin "2") (pinfunction "2_2") (pintype "passive"))
    )
    (net (code "40") (name "Net-(C10-Pad1)") (class "Default")
      (node (ref "C10") (pin "1") (pinfunction "1_1") (pintype "passive"))
      (node (ref "J6") (pin "2") (pinfunction "2_2") (pintype "passive"))
      (node (ref "R17") (pin "2") (pinfunction "2_2") (pintype "passive"))
    )
    (net (code "41") (name "Net-(D1-A1)") (class "Default")
      (node (ref "D1") (pin "1") (pinfunction "A1_1") (pintype "passive"))
      (node (ref "Q1") (pin "3") (pinfunction "D_3") (pintype "passive"))
    )
    (net (code "42") (name "Net-(D1-A2)") (class "Default")
      (node (ref "D1") (pin "2") (pinfunction "A2_2") (pintype "passive"))
      (node (ref "Q2") (pin "3") (pinfunction "D_3") (pintype "passive"))
    )
    (net (code "43") (name "Net-(D1-A3)") (class "Default")
      (node (ref "D1") (pin "6") (pinfunction "A3_6") (pintype "passive"))
      (node (ref "Q4") (pin "3") (pinfunction "D_3") (pintype "passive"))
    )
    (net (code "44") (name "Net-(D1-A4)") (class "Default")
      (node (ref "D1") (pin "8") (pinfunction "A4_8") (pintype "passive"))
      (node (ref "Q5") (pin "3") (pinfunction "D_3") (pintype "passive"))
    )
    (net (code "45") (name "Net-(D1-A_(L1))") (class "Default")
      (node (ref "D1") (pin "14") (pinfunction "A_(L1)_14") (pintype "passive"))
      (node (ref "R11") (pin "1") (pinfunction "1_1") (pintype "passive"))
    )
    (net (code "46") (name "Net-(D1-B_(L2))") (class "Default")
      (node (ref "D1") (pin "16") (pinfunction "B_(L2)_16") (pintype "passive"))
      (node (ref "R7") (pin "1") (pinfunction "1_1") (pintype "passive"))
    )
    (net (code "47") (name "Net-(D1-C_(L3))") (class "Default")
      (node (ref "D1") (pin "13") (pinfunction "C_(L3)_13") (pintype "passive"))
      (node (ref "R10") (pin "1") (pinfunction "1_1") (pintype "passive"))
    )
    (net (code "48") (name "Net-(D1-D)") (class "Default")
      (node (ref "D1") (pin "3") (pinfunction "D_3") (pintype "passive"))
      (node (ref "R8") (pin "1") (pinfunction "1_1") (pintype "passive"))
    )
    (net (code "49") (name "Net-(D1-DP)") (class "Default")
      (node (ref "D1") (pin "7") (pinfunction "DP_7") (pintype "passive"))
      (node (ref "R15") (pin "1") (pinfunction "1_1") (pintype "passive"))
    )
    (net (code "50") (name "Net-(D1-E)") (class "Default")
      (node (ref "D1") (pin "5") (pinfunction "E_5") (pintype "passive"))
      (node (ref "R14") (pin "1") (pinfunction "1_1") (pintype "passive"))
    )
    (net (code "51") (name "Net-(D1-F)") (class "Default")
      (node (ref "D1") (pin "11") (pinfunction "F_11") (pintype "passive"))
      (node (ref "R12") (pin "1") (pinfunction "1_1") (pintype "passive"))
    )
    (net (code "52") (name "Net-(D1-G)") (class "Default")
      (node (ref "D1") (pin "15") (pinfunction "G_15") (pintype "passive"))
      (node (ref "R9") (pin "1") (pinfunction "1_1") (pintype "passive"))
    )
    (net (code "53") (name "Net-(D1-L*)") (class "Default")
      (node (ref "D1") (pin "4") (pinfunction "L*_4") (pintype "passive"))
      (node (ref "Q3") (pin "3") (pinfunction "D_3") (pintype "passive"))
    )
    (net (code "54") (name "Net-(D2-PadA)") (class "Default")
      (node (ref "D2") (pin "A") (pinfunction "A_A") (pintype "passive"))
      (node (ref "R13") (pin "2") (pinfunction "2_2") (pintype "passive"))
    )
    (net (code "55") (name "Net-(J1-BLUE)") (class "Default")
      (node (ref "J1") (pin "3") (pinfunction "BLUE_3") (pintype "passive"))
      (node (ref "R5") (pin "2") (pinfunction "2_2") (pintype "passive"))
      (node (ref "R6") (pin "2") (pinfunction "2_2") (pintype "passive"))
    )
    (net (code "56") (name "Net-(J1-GREEN)") (class "Default")
      (node (ref "J1") (pin "2") (pinfunction "GREEN_2") (pintype "passive"))
      (node (ref "R3") (pin "2") (pinfunction "2_2") (pintype "passive"))
      (node (ref "R4") (pin "2") (pinfunction "2_2") (pintype "passive"))
    )
    (net (code "57") (name "Net-(J1-RED)") (class "Default")
      (node (ref "J1") (pin "1") (pinfunction "RED_1") (pintype "passive"))
      (node (ref "R1") (pin "2") (pinfunction "2_2") (pintype "passive"))
      (node (ref "R2") (pin "2") (pinfunction "2_2") (pintype "passive"))
    )
    (net (code "58") (name "VDD_PS2") (class "Default")
      (node (ref "C12") (pin "1") (pinfunction "1_1") (pintype "passive"))
      (node (ref "C14") (pin "1") (pinfunction "1_1") (pintype "passive"))
      (node (ref "C3") (pin "1") (pinfunction "1_1") (pintype "passive"))
      (node (ref "C4") (pin "1") (pinfunction "1_1") (pintype "passive"))
      (node (ref "C5") (pin "2") (pinfunction "2_2") (pintype "passive"))
      (node (ref "C6") (pin "2") (pinfunction "2_2") (pintype "passive"))
      (node (ref "J2") (pin "4") (pinfunction "VCC_4") (pintype "passive"))
      (node (ref "J3") (pin "4") (pinfunction "VCC_4") (pintype "passive"))
      (node (ref "JP1") (pin "1") (pinfunction "1_1") (pintype "passive"))
      (node (ref "P5") (pin "3") (pinfunction "3_3") (pintype "passive"))
      (node (ref "P5") (pin "7") (pinfunction "7_7") (pintype "passive"))
      (node (ref "P7") (pin "1") (pinfunction "1_1") (pintype "passive"))
      (node (ref "R13") (pin "1") (pinfunction "1_1") (pintype "passive"))
      (node (ref "R18") (pin "2") (pinfunction "2_2") (pintype "passive"))
      (node (ref "R19") (pin "2") (pinfunction "2_2") (pintype "passive"))
      (node (ref "R22") (pin "2") (pinfunction "2_2") (pintype "passive"))
      (node (ref "R23") (pin "2") (pinfunction "2_2") (pintype "passive"))
      (node (ref "U1") (pin "7") (pinfunction "VREFB_7") (pintype "passive"))
      (node (ref "U1") (pin "8") (pinfunction "EN_8") (pintype "passive"))
      (node (ref "U2") (pin "7") (pinfunction "VREFB_7") (pintype "passive"))
      (node (ref "U2") (pin "8") (pinfunction "EN_8") (pintype "passive"))
    )
    (net (code "59") (name "unconnected-(J1-ID0-Pad11)") (class "Default")
      (node (ref "J1") (pin "11") (pinfunction "ID0_11") (pintype "passive"))
    )
    (net (code "60") (name "unconnected-(J1-ID1{slash}SDA-Pad12)") (class "Default")
      (node (ref "J1") (pin "12") (pinfunction "ID1/SDA_12") (pintype "passive"))
    )
    (net (code "61") (name "unconnected-(J1-ID2-Pad4)") (class "Default")
      (node (ref "J1") (pin "4") (pinfunction "ID2_4") (pintype "passive"))
    )
    (net (code "62") (name "unconnected-(J1-ID3{slash}SCL-Pad15)") (class "Default")
      (node (ref "J1") (pin "15") (pinfunction "ID3/SCL_15") (pintype "passive"))
    )
    (net (code "63") (name "unconnected-(J1-KEY-Pad9)") (class "Default")
      (node (ref "J1") (pin "9") (pinfunction "KEY_9") (pintype "passive"))
    )
    (net (code "64") (name "unconnected-(J2-NC-Pad2)") (class "Default")
      (node (ref "J2") (pin "2") (pinfunction "NC_2") (pintype "passive+no_connect"))
    )
    (net (code "65") (name "unconnected-(J2-NC-Pad6)") (class "Default")
      (node (ref "J2") (pin "6") (pinfunction "NC_6") (pintype "passive+no_connect"))
    )
    (net (code "66") (name "unconnected-(J3-NC-Pad2)") (class "Default")
      (node (ref "J3") (pin "2") (pinfunction "NC_2") (pintype "passive+no_connect"))
    )
    (net (code "67") (name "unconnected-(J3-NC-Pad6)") (class "Default")
      (node (ref "J3") (pin "6") (pinfunction "NC_6") (pintype "passive+no_connect"))
    )
    (net (code "68") (name "unconnected-(P2-GND-Pad5)") (class "Default")
      (node (ref "P2") (pin "5") (pinfunction "GND_5") (pintype "power_in+no_connect"))
    )
    (net (code "69") (name "unconnected-(P2-GND-Pad11)") (class "Default")
      (node (ref "P2") (pin "11") (pinfunction "GND_11") (pintype "power_in+no_connect"))
    )
    (net (code "70") (name "unconnected-(P2-VCC-Pad6)") (class "Default")
      (node (ref "P2") (pin "6") (pinfunction "VCC_6") (pintype "power_in+no_connect"))
    )
    (net (code "71") (name "unconnected-(P2-VCC-Pad12)") (class "Default")
      (node (ref "P2") (pin "12") (pinfunction "VCC_12") (pintype "power_in+no_connect"))
    )
    (net (code "72") (name "unconnected-(P3-GND-Pad5)") (class "Default")
      (node (ref "P3") (pin "5") (pinfunction "GND_5") (pintype "power_in+no_connect"))
    )
    (net (code "73") (name "unconnected-(P3-GND-Pad11)") (class "Default")
      (node (ref "P3") (pin "11") (pinfunction "GND_11") (pintype "power_in+no_connect"))
    )
    (net (code "74") (name "unconnected-(P3-VCC-Pad6)") (class "Default")
      (node (ref "P3") (pin "6") (pinfunction "VCC_6") (pintype "power_in+no_connect"))
    )
    (net (code "75") (name "unconnected-(P3-VCC-Pad12)") (class "Default")
      (node (ref "P3") (pin "12") (pinfunction "VCC_12") (pintype "power_in+no_connect"))
    )
    (net (code "76") (name "unconnected-(P4-GND-Pad5)") (class "Default")
      (node (ref "P4") (pin "5") (pinfunction "GND_5") (pintype "power_in"))
    )
    (net (code "77") (name "unconnected-(P4-GND-Pad11)") (class "Default")
      (node (ref "P4") (pin "11") (pinfunction "GND_11") (pintype "power_in+no_connect"))
    )
    (net (code "78") (name "unconnected-(P4-VCC-Pad6)") (class "Default")
      (node (ref "P4") (pin "6") (pinfunction "VCC_6") (pintype "power_in"))
    )
    (net (code "79") (name "unconnected-(P4-VCC-Pad12)") (class "Default")
      (node (ref "P4") (pin "12") (pinfunction "VCC_12") (pintype "power_in+no_connect"))
    )
  )
)
